# IS903.net
KiCad netlist of a schematic drawn in Altium Designer
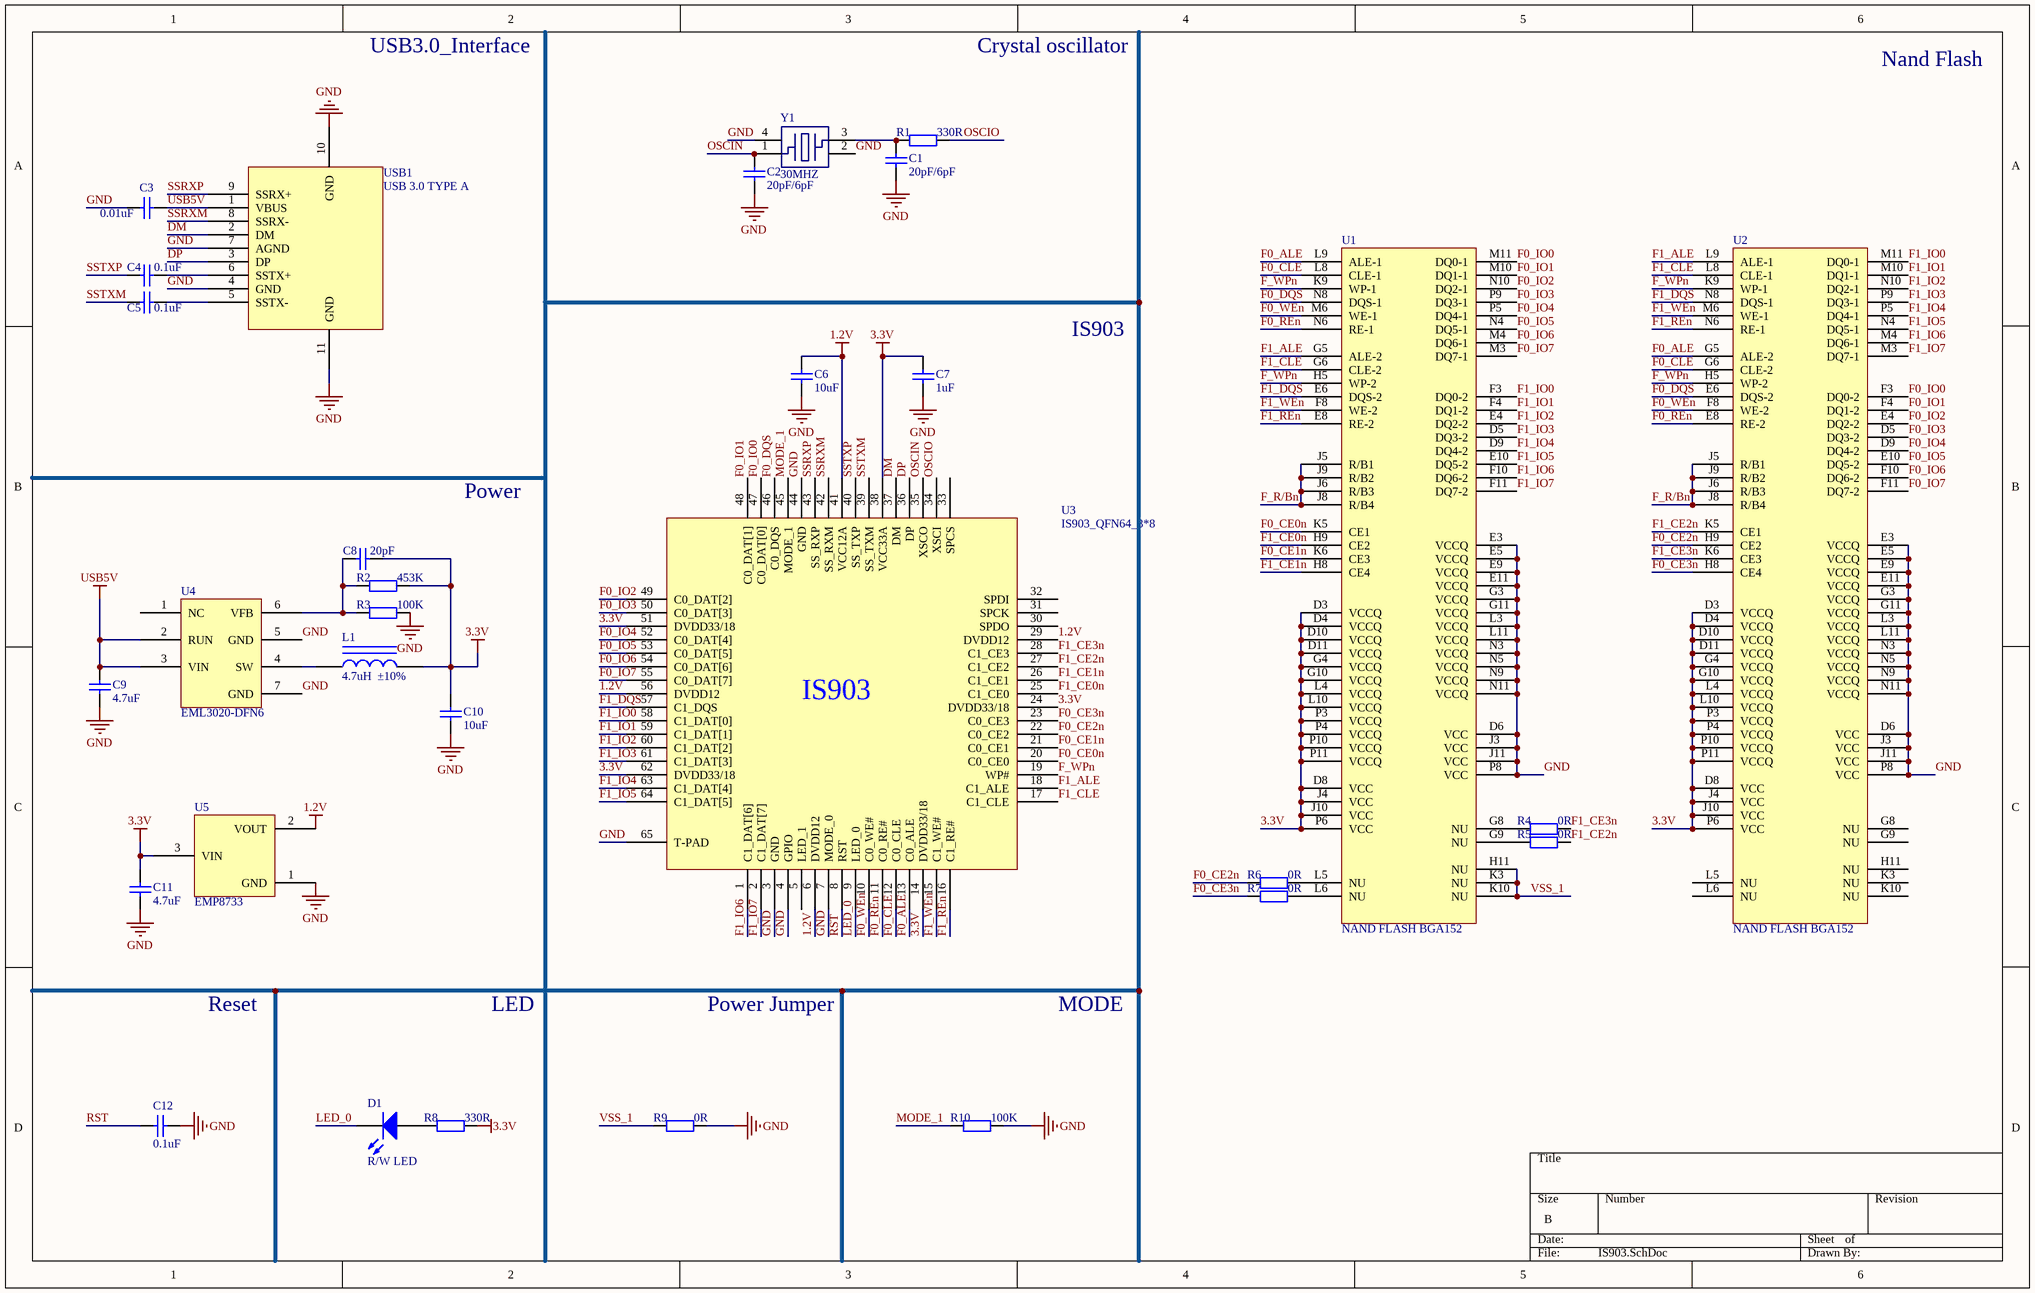
[diagram p0: IS903.SchDoc]

(export (version "E")
  (design (tool "Eeschema 10.0.6"))
  (components
    (comp (ref "C1")
      (value "20pF/6pF")
      (footprint "C 0402_L")
      (description "贴片电容")
      (libsource (lib "嘉立创") (part "0402 2.2nF (222) 10% 50V"))
    )
    (comp (ref "C2")
      (value "20pF/6pF")
      (footprint "C 0402_L")
      (description "贴片电容")
      (libsource (lib "嘉立创") (part "0402 2.2nF (222) 10% 50V"))
    )
    (comp (ref "C3")
      (value "0.01uF")
      (footprint "C 0402_L")
      (description "贴片电容")
      (libsource (lib "嘉立创") (part "0402 2.2nF (222) 10% 50V"))
    )
    (comp (ref "C4")
      (value "0.1uF")
      (footprint "C 0402_L")
      (description "贴片电容")
      (libsource (lib "嘉立创") (part "0402 2.2nF (222) 10% 50V"))
    )
    (comp (ref "C5")
      (value "0.1uF")
      (footprint "C 0402_L")
      (description "贴片电容")
      (libsource (lib "嘉立创") (part "0402 2.2nF (222) 10% 50V"))
    )
    (comp (ref "C6")
      (value "10uF")
      (footprint "C 0603_L")
      (description "贴片电容")
      (libsource (lib "嘉立创") (part "0603 100nF (104) 10% 50V"))
    )
    (comp (ref "C7")
      (value "1uF")
      (footprint "C 0402_L")
      (description "贴片电容")
      (libsource (lib "嘉立创") (part "0603 100nF (104) 10% 50V"))
    )
    (comp (ref "C8")
      (value "20pF")
      (footprint "C 0402_L")
      (description "贴片电容")
      (libsource (lib "嘉立创") (part "0402 2.2nF (222) 10% 50V"))
    )
    (comp (ref "C9")
      (value "4.7uF")
      (footprint "C 0603_L")
      (description "贴片电容")
      (libsource (lib "嘉立创") (part "0603 100nF (104) 10% 50V"))
    )
    (comp (ref "C10")
      (value "10uF")
      (footprint "C 0603_L")
      (description "贴片电容")
      (libsource (lib "嘉立创") (part "0603 100nF (104) 10% 50V"))
    )
    (comp (ref "C11")
      (value "4.7uF")
      (footprint "C 0603_L")
      (description "贴片电容")
      (libsource (lib "嘉立创") (part "0603 100nF (104) 10% 50V"))
    )
    (comp (ref "C12")
      (value "0.1uF")
      (footprint "C 0402_L")
      (description "贴片电容")
      (libsource (lib "嘉立创") (part "0402 2.2nF (222) 10% 50V"))
    )
    (comp (ref "D1")
      (value "R/W LED")
      (footprint "0603_LED_S1")
      (description "发光二极管")
      (libsource (lib "嘉立创") (part "0603 蓝灯"))
    )
    (comp (ref "L1")
      (value "4.7uH  ±10%")
      (footprint "LQM2HPN1R0MG0L")
      (description "贴片电感")
      (libsource (lib "嘉立创") (part "1206 4.7uH  10%"))
    )
    (comp (ref "R1")
      (value "330R")
      (footprint "R 0402_L")
      (description "贴片电阻")
      (libsource (lib "嘉立创") (part "0402 22Ω (22R0) 1%"))
    )
    (comp (ref "R2")
      (value "453K")
      (footprint "R 0402_L")
      (description "贴片电阻")
      (libsource (lib "嘉立创") (part "0402 22Ω (22R0) 1%"))
    )
    (comp (ref "R3")
      (value "100K")
      (footprint "R 0402_L")
      (description "贴片电阻")
      (libsource (lib "嘉立创") (part "0402 22Ω (22R0) 1%"))
    )
    (comp (ref "R4")
      (value "0R")
      (footprint "R 0402_L")
      (description "贴片电阻")
      (libsource (lib "嘉立创") (part "0402 22Ω (22R0) 1%"))
    )
    (comp (ref "R5")
      (value "0R")
      (footprint "R 0402_L")
      (description "贴片电阻")
      (libsource (lib "嘉立创") (part "0402 22Ω (22R0) 1%"))
    )
    (comp (ref "R6")
      (value "0R")
      (footprint "R 0402_L")
      (description "贴片电阻")
      (libsource (lib "嘉立创") (part "0402 22Ω (22R0) 1%"))
    )
    (comp (ref "R7")
      (value "0R")
      (footprint "R 0402_L")
      (description "贴片电阻")
      (libsource (lib "嘉立创") (part "0402 22Ω (22R0) 1%"))
    )
    (comp (ref "R8")
      (value "330R")
      (footprint "R 0402_L")
      (description "贴片电阻")
      (libsource (lib "嘉立创") (part "0402 22Ω (22R0) 1%"))
    )
    (comp (ref "R9")
      (value "0R")
      (footprint "R 0402_L")
      (description "贴片电阻")
      (libsource (lib "嘉立创") (part "0402 22Ω (22R0) 1%"))
    )
    (comp (ref "R10")
      (value "100K")
      (footprint "R 0402_L")
      (description "贴片电阻")
      (libsource (lib "嘉立创") (part "0402 22Ω (22R0) 1%"))
    )
    (comp (ref "U1")
      (value "NAND FLASH BGA152")
      (footprint "BGA152")
      (libsource (lib "IS903") (part "NAND FLASH BGA152"))
    )
    (comp (ref "U2")
      (value "NAND FLASH BGA152")
      (footprint "BGA152")
      (libsource (lib "IS903") (part "NAND FLASH BGA152"))
    )
    (comp (ref "U3")
      (value "IS903_QFN64_8*8")
      (footprint "QFN64 8x8_L")
      (libsource (lib "IS903") (part "IS903_QFN64_8*8"))
    )
    (comp (ref "U4")
      (value "EML3020-DFN6")
      (footprint "TDFN6")
      (libsource (lib "IS903") (part "EML3020-DFN6"))
    )
    (comp (ref "U5") (value "EMP8733") (footprint "SOT23-3L") (libsource (lib "IS903") (part "EMP8733")))
    (comp (ref "USB1")
      (value "USB 3.0 TYPE A")
      (footprint "USB3.0-G")
      (libsource (lib "IS903") (part "USB 3.0 TYPE A"))
    )
    (comp (ref "Y1") (value "30MHZ") (footprint "OSC 2025-4P") (libsource (lib "Schlib1") (part "晶振")))
  )
  (nets
    (net (code "1") (name "/DM") (class "Default")
      (node (ref "U3") (pin "37") (pinfunction "DM_37") (pintype "passive"))
      (node (ref "USB1") (pin "2") (pinfunction "DM_2") (pintype "passive"))
    )
    (net (code "2") (name "/DP") (class "Default")
      (node (ref "U3") (pin "36") (pinfunction "DP_36") (pintype "passive"))
      (node (ref "USB1") (pin "3") (pinfunction "DP_3") (pintype "passive"))
    )
    (net (code "3") (name "/F0_ALE") (class "Default")
      (node (ref "U1") (pin "L9") (pinfunction "ALE-1_L9") (pintype "passive"))
      (node (ref "U2") (pin "G5") (pinfunction "ALE-2_G5") (pintype "passive"))
      (node (ref "U3") (pin "13") (pinfunction "C0_ALE_13") (pintype "passive"))
    )
    (net (code "4") (name "/F0_CE0n") (class "Default")
      (node (ref "U1") (pin "K5") (pinfunction "CE1_K5") (pintype "passive"))
      (node (ref "U3") (pin "20") (pinfunction "C0_CE0_20") (pintype "passive"))
    )
    (net (code "5") (name "/F0_CE1n") (class "Default")
      (node (ref "U1") (pin "K6") (pinfunction "CE3_K6") (pintype "passive"))
      (node (ref "U3") (pin "21") (pinfunction "C0_CE1_21") (pintype "passive"))
    )
    (net (code "6") (name "/F0_CE2n") (class "Default")
      (node (ref "R6") (pin "1") (pinfunction "1_1") (pintype "passive"))
      (node (ref "U2") (pin "H9") (pinfunction "CE2_H9") (pintype "passive"))
      (node (ref "U3") (pin "22") (pinfunction "C0_CE2_22") (pintype "passive"))
    )
    (net (code "7") (name "/F0_CE3n") (class "Default")
      (node (ref "R7") (pin "1") (pinfunction "1_1") (pintype "passive"))
      (node (ref "U2") (pin "H8") (pinfunction "CE4_H8") (pintype "passive"))
      (node (ref "U3") (pin "23") (pinfunction "C0_CE3_23") (pintype "passive"))
    )
    (net (code "8") (name "/F0_CLE") (class "Default")
      (node (ref "U1") (pin "L8") (pinfunction "CLE-1_L8") (pintype "passive"))
      (node (ref "U2") (pin "G6") (pinfunction "CLE-2_G6") (pintype "passive"))
      (node (ref "U3") (pin "12") (pinfunction "C0_CLE_12") (pintype "passive"))
    )
    (net (code "9") (name "/F0_DQS") (class "Default")
      (node (ref "U1") (pin "N8") (pinfunction "DQS-1_N8") (pintype "passive"))
      (node (ref "U2") (pin "E6") (pinfunction "DQS-2_E6") (pintype "passive"))
      (node (ref "U3") (pin "46") (pinfunction "C0_DQS_46") (pintype "passive"))
    )
    (net (code "10") (name "/F0_IO0") (class "Default")
      (node (ref "U1") (pin "M11") (pinfunction "DQ0-1_M11") (pintype "passive"))
      (node (ref "U2") (pin "F3") (pinfunction "DQ0-2_F3") (pintype "passive"))
      (node (ref "U3") (pin "47") (pinfunction "C0_DAT[0]_47") (pintype "passive"))
    )
    (net (code "11") (name "/F0_IO1") (class "Default")
      (node (ref "U1") (pin "M10") (pinfunction "DQ1-1_M10") (pintype "passive"))
      (node (ref "U2") (pin "F4") (pinfunction "DQ1-2_F4") (pintype "passive"))
      (node (ref "U3") (pin "48") (pinfunction "C0_DAT[1]_48") (pintype "passive"))
    )
    (net (code "12") (name "/F0_IO2") (class "Default")
      (node (ref "U1") (pin "N10") (pinfunction "DQ2-1_N10") (pintype "passive"))
      (node (ref "U2") (pin "E4") (pinfunction "DQ2-2_E4") (pintype "passive"))
      (node (ref "U3") (pin "49") (pinfunction "C0_DAT[2]_49") (pintype "passive"))
    )
    (net (code "13") (name "/F0_IO3") (class "Default")
      (node (ref "U1") (pin "P9") (pinfunction "DQ3-1_P9") (pintype "passive"))
      (node (ref "U2") (pin "D5") (pinfunction "DQ3-2_D5") (pintype "passive"))
      (node (ref "U3") (pin "50") (pinfunction "C0_DAT[3]_50") (pintype "passive"))
    )
    (net (code "14") (name "/F0_IO4") (class "Default")
      (node (ref "U1") (pin "P5") (pinfunction "DQ4-1_P5") (pintype "passive"))
      (node (ref "U2") (pin "D9") (pinfunction "DQ4-2_D9") (pintype "passive"))
      (node (ref "U3") (pin "52") (pinfunction "C0_DAT[4]_52") (pintype "passive"))
    )
    (net (code "15") (name "/F0_IO5") (class "Default")
      (node (ref "U1") (pin "N4") (pinfunction "DQ5-1_N4") (pintype "passive"))
      (node (ref "U2") (pin "E10") (pinfunction "DQ5-2_E10") (pintype "passive"))
      (node (ref "U3") (pin "53") (pinfunction "C0_DAT[5]_53") (pintype "passive"))
    )
    (net (code "16") (name "/F0_IO6") (class "Default")
      (node (ref "U1") (pin "M4") (pinfunction "DQ6-1_M4") (pintype "passive"))
      (node (ref "U2") (pin "F10") (pinfunction "DQ6-2_F10") (pintype "passive"))
      (node (ref "U3") (pin "54") (pinfunction "C0_DAT[6]_54") (pintype "passive"))
    )
    (net (code "17") (name "/F0_IO7") (class "Default")
      (node (ref "U1") (pin "M3") (pinfunction "DQ7-1_M3") (pintype "passive"))
      (node (ref "U2") (pin "F11") (pinfunction "DQ7-2_F11") (pintype "passive"))
      (node (ref "U3") (pin "55") (pinfunction "C0_DAT[7]_55") (pintype "passive"))
    )
    (net (code "18") (name "/F0_REn") (class "Default")
      (node (ref "U1") (pin "N6") (pinfunction "RE-1_N6") (pintype "passive"))
      (node (ref "U2") (pin "E8") (pinfunction "RE-2_E8") (pintype "passive"))
      (node (ref "U3") (pin "11") (pinfunction "C0_RE#_11") (pintype "passive"))
    )
    (net (code "19") (name "/F0_WEn") (class "Default")
      (node (ref "U1") (pin "M6") (pinfunction "WE-1_M6") (pintype "passive"))
      (node (ref "U2") (pin "F8") (pinfunction "WE-2_F8") (pintype "passive"))
      (node (ref "U3") (pin "10") (pinfunction "C0_WE#_10") (pintype "passive"))
    )
    (net (code "20") (name "/F1_ALE") (class "Default")
      (node (ref "U1") (pin "G5") (pinfunction "ALE-2_G5") (pintype "passive"))
      (node (ref "U2") (pin "L9") (pinfunction "ALE-1_L9") (pintype "passive"))
      (node (ref "U3") (pin "18") (pinfunction "C1_ALE_18") (pintype "passive"))
    )
    (net (code "21") (name "/F1_CE0n") (class "Default")
      (node (ref "U1") (pin "H9") (pinfunction "CE2_H9") (pintype "passive"))
      (node (ref "U3") (pin "25") (pinfunction "C1_CE0_25") (pintype "passive"))
    )
    (net (code "22") (name "/F1_CE1n") (class "Default")
      (node (ref "U1") (pin "H8") (pinfunction "CE4_H8") (pintype "passive"))
      (node (ref "U3") (pin "26") (pinfunction "C1_CE1_26") (pintype "passive"))
    )
    (net (code "23") (name "/F1_CE2n") (class "Default")
      (node (ref "R5") (pin "2") (pinfunction "2_2") (pintype "passive"))
      (node (ref "U2") (pin "K5") (pinfunction "CE1_K5") (pintype "passive"))
      (node (ref "U3") (pin "27") (pinfunction "C1_CE2_27") (pintype "passive"))
    )
    (net (code "24") (name "/F1_CE3n") (class "Default")
      (node (ref "R4") (pin "2") (pinfunction "2_2") (pintype "passive"))
      (node (ref "U2") (pin "K6") (pinfunction "CE3_K6") (pintype "passive"))
      (node (ref "U3") (pin "28") (pinfunction "C1_CE3_28") (pintype "passive"))
    )
    (net (code "25") (name "/F1_CLE") (class "Default")
      (node (ref "U1") (pin "G6") (pinfunction "CLE-2_G6") (pintype "passive"))
      (node (ref "U2") (pin "L8") (pinfunction "CLE-1_L8") (pintype "passive"))
      (node (ref "U3") (pin "17") (pinfunction "C1_CLE_17") (pintype "passive"))
    )
    (net (code "26") (name "/F1_DQS") (class "Default")
      (node (ref "U1") (pin "E6") (pinfunction "DQS-2_E6") (pintype "passive"))
      (node (ref "U2") (pin "N8") (pinfunction "DQS-1_N8") (pintype "passive"))
      (node (ref "U3") (pin "57") (pinfunction "C1_DQS_57") (pintype "passive"))
    )
    (net (code "27") (name "/F1_IO0") (class "Default")
      (node (ref "U1") (pin "F3") (pinfunction "DQ0-2_F3") (pintype "passive"))
      (node (ref "U2") (pin "M11") (pinfunction "DQ0-1_M11") (pintype "passive"))
      (node (ref "U3") (pin "58") (pinfunction "C1_DAT[0]_58") (pintype "passive"))
    )
    (net (code "28") (name "/F1_IO1") (class "Default")
      (node (ref "U1") (pin "F4") (pinfunction "DQ1-2_F4") (pintype "passive"))
      (node (ref "U2") (pin "M10") (pinfunction "DQ1-1_M10") (pintype "passive"))
      (node (ref "U3") (pin "59") (pinfunction "C1_DAT[1]_59") (pintype "passive"))
    )
    (net (code "29") (name "/F1_IO2") (class "Default")
      (node (ref "U1") (pin "E4") (pinfunction "DQ2-2_E4") (pintype "passive"))
      (node (ref "U2") (pin "N10") (pinfunction "DQ2-1_N10") (pintype "passive"))
      (node (ref "U3") (pin "60") (pinfunction "C1_DAT[2]_60") (pintype "passive"))
    )
    (net (code "30") (name "/F1_IO3") (class "Default")
      (node (ref "U1") (pin "D5") (pinfunction "DQ3-2_D5") (pintype "passive"))
      (node (ref "U2") (pin "P9") (pinfunction "DQ3-1_P9") (pintype "passive"))
      (node (ref "U3") (pin "61") (pinfunction "C1_DAT[3]_61") (pintype "passive"))
    )
    (net (code "31") (name "/F1_IO4") (class "Default")
      (node (ref "U1") (pin "D9") (pinfunction "DQ4-2_D9") (pintype "passive"))
      (node (ref "U2") (pin "P5") (pinfunction "DQ4-1_P5") (pintype "passive"))
      (node (ref "U3") (pin "63") (pinfunction "C1_DAT[4]_63") (pintype "passive"))
    )
    (net (code "32") (name "/F1_IO5") (class "Default")
      (node (ref "U1") (pin "E10") (pinfunction "DQ5-2_E10") (pintype "passive"))
      (node (ref "U2") (pin "N4") (pinfunction "DQ5-1_N4") (pintype "passive"))
      (node (ref "U3") (pin "64") (pinfunction "C1_DAT[5]_64") (pintype "passive"))
    )
    (net (code "33") (name "/F1_IO6") (class "Default")
      (node (ref "U1") (pin "F10") (pinfunction "DQ6-2_F10") (pintype "passive"))
      (node (ref "U2") (pin "M4") (pinfunction "DQ6-1_M4") (pintype "passive"))
      (node (ref "U3") (pin "1") (pinfunction "C1_DAT[6]_1") (pintype "passive"))
    )
    (net (code "34") (name "/F1_IO7") (class "Default")
      (node (ref "U1") (pin "F11") (pinfunction "DQ7-2_F11") (pintype "passive"))
      (node (ref "U2") (pin "M3") (pinfunction "DQ7-1_M3") (pintype "passive"))
      (node (ref "U3") (pin "2") (pinfunction "C1_DAT[7]_2") (pintype "passive"))
    )
    (net (code "35") (name "/F1_REn") (class "Default")
      (node (ref "U1") (pin "E8") (pinfunction "RE-2_E8") (pintype "passive"))
      (node (ref "U2") (pin "N6") (pinfunction "RE-1_N6") (pintype "passive"))
      (node (ref "U3") (pin "16") (pinfunction "C1_RE#_16") (pintype "passive"))
    )
    (net (code "36") (name "/F1_WEn") (class "Default")
      (node (ref "U1") (pin "F8") (pinfunction "WE-2_F8") (pintype "passive"))
      (node (ref "U2") (pin "M6") (pinfunction "WE-1_M6") (pintype "passive"))
      (node (ref "U3") (pin "15") (pinfunction "C1_WE#_15") (pintype "passive"))
    )
    (net (code "37") (name "/F_R{slash}Bn") (class "Default")
      (node (ref "U1") (pin "J5") (pinfunction "R/B1_J5") (pintype "passive"))
      (node (ref "U1") (pin "J6") (pinfunction "R/B3_J6") (pintype "passive"))
      (node (ref "U1") (pin "J8") (pinfunction "R/B4_J8") (pintype "passive"))
      (node (ref "U1") (pin "J9") (pinfunction "R/B2_J9") (pintype "passive"))
      (node (ref "U2") (pin "J5") (pinfunction "R/B1_J5") (pintype "passive"))
      (node (ref "U2") (pin "J6") (pinfunction "R/B3_J6") (pintype "passive"))
      (node (ref "U2") (pin "J8") (pinfunction "R/B4_J8") (pintype "passive"))
      (node (ref "U2") (pin "J9") (pinfunction "R/B2_J9") (pintype "passive"))
    )
    (net (code "38") (name "/F_WPn") (class "Default")
      (node (ref "U1") (pin "H5") (pinfunction "WP-2_H5") (pintype "passive"))
      (node (ref "U1") (pin "K9") (pinfunction "WP-1_K9") (pintype "passive"))
      (node (ref "U2") (pin "H5") (pinfunction "WP-2_H5") (pintype "passive"))
      (node (ref "U2") (pin "K9") (pinfunction "WP-1_K9") (pintype "passive"))
      (node (ref "U3") (pin "19") (pinfunction "WP#_19") (pintype "passive"))
    )
    (net (code "39") (name "/LED_0") (class "Default")
      (node (ref "D1") (pin "K") (pinfunction "K_K") (pintype "passive"))
      (node (ref "U3") (pin "9") (pinfunction "LED_0_9") (pintype "passive"))
    )
    (net (code "40") (name "/MODE_1") (class "Default")
      (node (ref "R10") (pin "1") (pinfunction "1_1") (pintype "passive"))
      (node (ref "U3") (pin "45") (pinfunction "MODE_1_45") (pintype "passive"))
    )
    (net (code "41") (name "/OSCIN") (class "Default")
      (node (ref "C2") (pin "1") (pinfunction "1_1") (pintype "passive"))
      (node (ref "U3") (pin "35") (pinfunction "XSCO_35") (pintype "passive"))
      (node (ref "Y1") (pin "1") (pinfunction "1_1") (pintype "passive"))
    )
    (net (code "42") (name "/OSCIO") (class "Default")
      (node (ref "R1") (pin "2") (pinfunction "2_2") (pintype "passive"))
      (node (ref "U3") (pin "34") (pinfunction "XSCI_34") (pintype "passive"))
    )
    (net (code "43") (name "/RST") (class "Default")
      (node (ref "C12") (pin "1") (pinfunction "1_1") (pintype "passive"))
      (node (ref "U3") (pin "8") (pinfunction "RST_8") (pintype "passive"))
    )
    (net (code "44") (name "/SSRXM") (class "Default")
      (node (ref "U3") (pin "42") (pinfunction "SS_RXM_42") (pintype "passive"))
      (node (ref "USB1") (pin "8") (pinfunction "SSRX-_8") (pintype "passive"))
    )
    (net (code "45") (name "/SSRXP") (class "Default")
      (node (ref "U3") (pin "43") (pinfunction "SS_RXP_43") (pintype "passive"))
      (node (ref "USB1") (pin "9") (pinfunction "SSRX+_9") (pintype "passive"))
    )
    (net (code "46") (name "/SSTXM") (class "Default")
      (node (ref "C5") (pin "2") (pinfunction "2_2") (pintype "passive"))
      (node (ref "U3") (pin "39") (pinfunction "SS_TXM_39") (pintype "passive"))
    )
    (net (code "47") (name "/SSTXP") (class "Default")
      (node (ref "C4") (pin "2") (pinfunction "2_2") (pintype "passive"))
      (node (ref "U3") (pin "40") (pinfunction "SS_TXP_40") (pintype "passive"))
    )
    (net (code "48") (name "/VSS_1") (class "Default")
      (node (ref "R9") (pin "1") (pinfunction "1_1") (pintype "passive"))
      (node (ref "U1") (pin "H11") (pinfunction "NU_H11") (pintype "passive"))
      (node (ref "U1") (pin "K10") (pinfunction "NU_K10") (pintype "passive"))
      (node (ref "U1") (pin "K3") (pinfunction "NU_K3") (pintype "passive"))
    )
    (net (code "49") (name "1.2V") (class "Default")
      (node (ref "C6") (pin "2") (pinfunction "2_2") (pintype "passive"))
      (node (ref "U3") (pin "29") (pinfunction "DVDD12_29") (pintype "passive"))
      (node (ref "U3") (pin "41") (pinfunction "VCC12A_41") (pintype "passive"))
      (node (ref "U3") (pin "56") (pinfunction "DVDD12_56") (pintype "passive"))
      (node (ref "U3") (pin "6") (pinfunction "DVDD12_6") (pintype "passive"))
      (node (ref "U5") (pin "2") (pinfunction "VOUT_2") (pintype "passive"))
    )
    (net (code "50") (name "3.3V") (class "Default")
      (node (ref "C10") (pin "2") (pinfunction "2_2") (pintype "passive"))
      (node (ref "C11") (pin "2") (pinfunction "2_2") (pintype "passive"))
      (node (ref "C7") (pin "2") (pinfunction "2_2") (pintype "passive"))
      (node (ref "C8") (pin "1") (pinfunction "1_1") (pintype "passive"))
      (node (ref "L1") (pin "2") (pinfunction "2_2") (pintype "passive"))
      (node (ref "R2") (pin "2") (pinfunction "2_2") (pintype "passive"))
      (node (ref "R8") (pin "2") (pinfunction "2_2") (pintype "passive"))
      (node (ref "U1") (pin "D10") (pinfunction "VCCQ_D10") (pintype "passive"))
      (node (ref "U1") (pin "D11") (pinfunction "VCCQ_D11") (pintype "passive"))
      (node (ref "U1") (pin "D3") (pinfunction "VCCQ_D3") (pintype "passive"))
      (node (ref "U1") (pin "D4") (pinfunction "VCCQ_D4") (pintype "passive"))
      (node (ref "U1") (pin "D8") (pinfunction "VCC_D8") (pintype "passive"))
      (node (ref "U1") (pin "G10") (pinfunction "VCCQ_G10") (pintype "passive"))
      (node (ref "U1") (pin "G4") (pinfunction "VCCQ_G4") (pintype "passive"))
      (node (ref "U1") (pin "J10") (pinfunction "VCC_J10") (pintype "passive"))
      (node (ref "U1") (pin "J4") (pinfunction "VCC_J4") (pintype "passive"))
      (node (ref "U1") (pin "L10") (pinfunction "VCCQ_L10") (pintype "passive"))
      (node (ref "U1") (pin "L4") (pinfunction "VCCQ_L4") (pintype "passive"))
      (node (ref "U1") (pin "P10") (pinfunction "VCCQ_P10") (pintype "passive"))
      (node (ref "U1") (pin "P11") (pinfunction "VCCQ_P11") (pintype "passive"))
      (node (ref "U1") (pin "P3") (pinfunction "VCCQ_P3") (pintype "passive"))
      (node (ref "U1") (pin "P4") (pinfunction "VCCQ_P4") (pintype "passive"))
      (node (ref "U1") (pin "P6") (pinfunction "VCC_P6") (pintype "passive"))
      (node (ref "U2") (pin "D10") (pinfunction "VCCQ_D10") (pintype "passive"))
      (node (ref "U2") (pin "D11") (pinfunction "VCCQ_D11") (pintype "passive"))
      (node (ref "U2") (pin "D3") (pinfunction "VCCQ_D3") (pintype "passive"))
      (node (ref "U2") (pin "D4") (pinfunction "VCCQ_D4") (pintype "passive"))
      (node (ref "U2") (pin "D8") (pinfunction "VCC_D8") (pintype "passive"))
      (node (ref "U2") (pin "G10") (pinfunction "VCCQ_G10") (pintype "passive"))
      (node (ref "U2") (pin "G4") (pinfunction "VCCQ_G4") (pintype "passive"))
      (node (ref "U2") (pin "J10") (pinfunction "VCC_J10") (pintype "passive"))
      (node (ref "U2") (pin "J4") (pinfunction "VCC_J4") (pintype "passive"))
      (node (ref "U2") (pin "L10") (pinfunction "VCCQ_L10") (pintype "passive"))
      (node (ref "U2") (pin "L4") (pinfunction "VCCQ_L4") (pintype "passive"))
      (node (ref "U2") (pin "P10") (pinfunction "VCCQ_P10") (pintype "passive"))
      (node (ref "U2") (pin "P11") (pinfunction "VCCQ_P11") (pintype "passive"))
      (node (ref "U2") (pin "P3") (pinfunction "VCCQ_P3") (pintype "passive"))
      (node (ref "U2") (pin "P4") (pinfunction "VCCQ_P4") (pintype "passive"))
      (node (ref "U2") (pin "P6") (pinfunction "VCC_P6") (pintype "passive"))
      (node (ref "U3") (pin "14") (pinfunction "DVDD33/18_14") (pintype "passive"))
      (node (ref "U3") (pin "24") (pinfunction "DVDD33/18_24") (pintype "passive"))
      (node (ref "U3") (pin "38") (pinfunction "VCC33A_38") (pintype "passive"))
      (node (ref "U3") (pin "51") (pinfunction "DVDD33/18_51") (pintype "passive"))
      (node (ref "U3") (pin "62") (pinfunction "DVDD33/18_62") (pintype "passive"))
      (node (ref "U5") (pin "3") (pinfunction "VIN_3") (pintype "passive"))
    )
    (net (code "51") (name "GND") (class "Default")
      (node (ref "C1") (pin "2") (pinfunction "2_2") (pintype "passive"))
      (node (ref "C10") (pin "1") (pinfunction "1_1") (pintype "passive"))
      (node (ref "C11") (pin "1") (pinfunction "1_1") (pintype "passive"))
      (node (ref "C12") (pin "2") (pinfunction "2_2") (pintype "passive"))
      (node (ref "C2") (pin "2") (pinfunction "2_2") (pintype "passive"))
      (node (ref "C3") (pin "2") (pinfunction "2_2") (pintype "passive"))
      (node (ref "C6") (pin "1") (pinfunction "1_1") (pintype "passive"))
      (node (ref "C7") (pin "1") (pinfunction "1_1") (pintype "passive"))
      (node (ref "C9") (pin "1") (pinfunction "1_1") (pintype "passive"))
      (node (ref "R10") (pin "2") (pinfunction "2_2") (pintype "passive"))
      (node (ref "R3") (pin "2") (pinfunction "2_2") (pintype "passive"))
      (node (ref "R9") (pin "2") (pinfunction "2_2") (pintype "passive"))
      (node (ref "U1") (pin "D6") (pinfunction "VCC_D6") (pintype "passive"))
      (node (ref "U1") (pin "E11") (pinfunction "VCCQ_E11") (pintype "passive"))
      (node (ref "U1") (pin "E3") (pinfunction "VCCQ_E3") (pintype "passive"))
      (node (ref "U1") (pin "E5") (pinfunction "VCCQ_E5") (pintype "passive"))
      (node (ref "U1") (pin "E9") (pinfunction "VCCQ_E9") (pintype "passive"))
      (node (ref "U1") (pin "G11") (pinfunction "VCCQ_G11") (pintype "passive"))
      (node (ref "U1") (pin "G3") (pinfunction "VCCQ_G3") (pintype "passive"))
      (node (ref "U1") (pin "J11") (pinfunction "VCC_J11") (pintype "passive"))
      (node (ref "U1") (pin "J3") (pinfunction "VCC_J3") (pintype "passive"))
      (node (ref "U1") (pin "L11") (pinfunction "VCCQ_L11") (pintype "passive"))
      (node (ref "U1") (pin "L3") (pinfunction "VCCQ_L3") (pintype "passive"))
      (node (ref "U1") (pin "N11") (pinfunction "VCCQ_N11") (pintype "passive"))
      (node (ref "U1") (pin "N3") (pinfunction "VCCQ_N3") (pintype "passive"))
      (node (ref "U1") (pin "N5") (pinfunction "VCCQ_N5") (pintype "passive"))
      (node (ref "U1") (pin "N9") (pinfunction "VCCQ_N9") (pintype "passive"))
      (node (ref "U1") (pin "P8") (pinfunction "VCC_P8") (pintype "passive"))
      (node (ref "U2") (pin "D6") (pinfunction "VCC_D6") (pintype "passive"))
      (node (ref "U2") (pin "E11") (pinfunction "VCCQ_E11") (pintype "passive"))
      (node (ref "U2") (pin "E3") (pinfunction "VCCQ_E3") (pintype "passive"))
      (node (ref "U2") (pin "E5") (pinfunction "VCCQ_E5") (pintype "passive"))
      (node (ref "U2") (pin "E9") (pinfunction "VCCQ_E9") (pintype "passive"))
      (node (ref "U2") (pin "G11") (pinfunction "VCCQ_G11") (pintype "passive"))
      (node (ref "U2") (pin "G3") (pinfunction "VCCQ_G3") (pintype "passive"))
      (node (ref "U2") (pin "J11") (pinfunction "VCC_J11") (pintype "passive"))
      (node (ref "U2") (pin "J3") (pinfunction "VCC_J3") (pintype "passive"))
      (node (ref "U2") (pin "L11") (pinfunction "VCCQ_L11") (pintype "passive"))
      (node (ref "U2") (pin "L3") (pinfunction "VCCQ_L3") (pintype "passive"))
      (node (ref "U2") (pin "N11") (pinfunction "VCCQ_N11") (pintype "passive"))
      (node (ref "U2") (pin "N3") (pinfunction "VCCQ_N3") (pintype "passive"))
      (node (ref "U2") (pin "N5") (pinfunction "VCCQ_N5") (pintype "passive"))
      (node (ref "U2") (pin "N9") (pinfunction "VCCQ_N9") (pintype "passive"))
      (node (ref "U2") (pin "P8") (pinfunction "VCC_P8") (pintype "passive"))
      (node (ref "U3") (pin "3") (pinfunction "GND_3") (pintype "passive"))
      (node (ref "U3") (pin "4") (pinfunction "GPIO_4") (pintype "passive"))
      (node (ref "U3") (pin "44") (pinfunction "GND_44") (pintype "passive"))
      (node (ref "U3") (pin "65") (pinfunction "T-PAD_65") (pintype "passive"))
      (node (ref "U3") (pin "7") (pinfunction "MODE_0_7") (pintype "passive"))
      (node (ref "U4") (pin "5") (pinfunction "GND_5") (pintype "passive"))
      (node (ref "U4") (pin "7") (pinfunction "GND_7") (pintype "passive"))
      (node (ref "U5") (pin "1") (pinfunction "GND_1") (pintype "passive"))
      (node (ref "USB1") (pin "10") (pinfunction "GND_10") (pintype "passive"))
      (node (ref "USB1") (pin "11") (pinfunction "GND_11") (pintype "passive"))
      (node (ref "USB1") (pin "4") (pinfunction "GND_4") (pintype "passive"))
      (node (ref "USB1") (pin "7") (pinfunction "AGND_7") (pintype "passive"))
      (node (ref "Y1") (pin "2") (pinfunction "2_2") (pintype "passive"))
      (node (ref "Y1") (pin "4") (pinfunction "4_4") (pintype "passive"))
    )
    (net (code "52") (name "Net-(C1-Pad1)") (class "Default")
      (node (ref "C1") (pin "1") (pinfunction "1_1") (pintype "passive"))
      (node (ref "R1") (pin "1") (pinfunction "1_1") (pintype "passive"))
      (node (ref "Y1") (pin "3") (pinfunction "3_3") (pintype "passive"))
    )
    (net (code "53") (name "Net-(D1-PadA)") (class "Default")
      (node (ref "D1") (pin "A") (pinfunction "A_A") (pintype "passive"))
      (node (ref "R8") (pin "1") (pinfunction "1_1") (pintype "passive"))
    )
    (net (code "54") (name "Net-(R4-Pad1)") (class "Default")
      (node (ref "R4") (pin "1") (pinfunction "1_1") (pintype "passive"))
      (node (ref "U1") (pin "G8") (pinfunction "NU_G8") (pintype "passive"))
    )
    (net (code "55") (name "Net-(R5-Pad1)") (class "Default")
      (node (ref "R5") (pin "1") (pinfunction "1_1") (pintype "passive"))
      (node (ref "U1") (pin "G9") (pinfunction "NU_G9") (pintype "passive"))
    )
    (net (code "56") (name "Net-(R6-Pad2)") (class "Default")
      (node (ref "R6") (pin "2") (pinfunction "2_2") (pintype "passive"))
      (node (ref "U1") (pin "L5") (pinfunction "NU_L5") (pintype "passive"))
    )
    (net (code "57") (name "Net-(R7-Pad2)") (class "Default")
      (node (ref "R7") (pin "2") (pinfunction "2_2") (pintype "passive"))
      (node (ref "U1") (pin "L6") (pinfunction "NU_L6") (pintype "passive"))
    )
    (net (code "58") (name "Net-(U4-SW)") (class "Default")
      (node (ref "L1") (pin "1") (pinfunction "1_1") (pintype "passive"))
      (node (ref "U4") (pin "4") (pinfunction "SW_4") (pintype "passive"))
    )
    (net (code "59") (name "Net-(U4-VFB)") (class "Default")
      (node (ref "C8") (pin "2") (pinfunction "2_2") (pintype "passive"))
      (node (ref "R2") (pin "1") (pinfunction "1_1") (pintype "passive"))
      (node (ref "R3") (pin "1") (pinfunction "1_1") (pintype "passive"))
      (node (ref "U4") (pin "6") (pinfunction "VFB_6") (pintype "passive"))
    )
    (net (code "60") (name "Net-(USB1-SSTX+)") (class "Default")
      (node (ref "C4") (pin "1") (pinfunction "1_1") (pintype "passive"))
      (node (ref "USB1") (pin "6") (pinfunction "SSTX+_6") (pintype "passive"))
    )
    (net (code "61") (name "Net-(USB1-SSTX-)") (class "Default")
      (node (ref "C5") (pin "1") (pinfunction "1_1") (pintype "passive"))
      (node (ref "USB1") (pin "5") (pinfunction "SSTX-_5") (pintype "passive"))
    )
    (net (code "62") (name "USB5V") (class "Default")
      (node (ref "C3") (pin "1") (pinfunction "1_1") (pintype "passive"))
      (node (ref "C9") (pin "2") (pinfunction "2_2") (pintype "passive"))
      (node (ref "U4") (pin "2") (pinfunction "RUN_2") (pintype "passive"))
      (node (ref "U4") (pin "3") (pinfunction "VIN_3") (pintype "passive"))
      (node (ref "USB1") (pin "1") (pinfunction "VBUS_1") (pintype "passive"))
    )
    (net (code "63") (name "unconnected-(U2-NU-PadG8)") (class "Default")
      (node (ref "U2") (pin "G8") (pinfunction "NU_G8") (pintype "passive"))
    )
    (net (code "64") (name "unconnected-(U2-NU-PadG9)") (class "Default")
      (node (ref "U2") (pin "G9") (pinfunction "NU_G9") (pintype "passive"))
    )
    (net (code "65") (name "unconnected-(U2-NU-PadH11)") (class "Default")
      (node (ref "U2") (pin "H11") (pinfunction "NU_H11") (pintype "passive"))
    )
    (net (code "66") (name "unconnected-(U2-NU-PadK3)") (class "Default")
      (node (ref "U2") (pin "K3") (pinfunction "NU_K3") (pintype "passive"))
    )
    (net (code "67") (name "unconnected-(U2-NU-PadK10)") (class "Default")
      (node (ref "U2") (pin "K10") (pinfunction "NU_K10") (pintype "passive"))
    )
    (net (code "68") (name "unconnected-(U2-NU-PadL5)") (class "Default")
      (node (ref "U2") (pin "L5") (pinfunction "NU_L5") (pintype "passive"))
    )
    (net (code "69") (name "unconnected-(U2-NU-PadL6)") (class "Default")
      (node (ref "U2") (pin "L6") (pinfunction "NU_L6") (pintype "passive"))
    )
    (net (code "70") (name "unconnected-(U3-LED_1-Pad5)") (class "Default")
      (node (ref "U3") (pin "5") (pinfunction "LED_1_5") (pintype "passive"))
    )
    (net (code "71") (name "unconnected-(U3-SPCK-Pad31)") (class "Default")
      (node (ref "U3") (pin "31") (pinfunction "SPCK_31") (pintype "passive"))
    )
    (net (code "72") (name "unconnected-(U3-SPCS-Pad33)") (class "Default")
      (node (ref "U3") (pin "33") (pinfunction "SPCS_33") (pintype "passive"))
    )
    (net (code "73") (name "unconnected-(U3-SPDI-Pad32)") (class "Default")
      (node (ref "U3") (pin "32") (pinfunction "SPDI_32") (pintype "passive"))
    )
    (net (code "74") (name "unconnected-(U3-SPDO-Pad30)") (class "Default")
      (node (ref "U3") (pin "30") (pinfunction "SPDO_30") (pintype "passive"))
    )
    (net (code "75") (name "unconnected-(U4-NC-Pad1)") (class "Default")
      (node (ref "U4") (pin "1") (pinfunction "NC_1") (pintype "passive"))
    )
  )
)
